# rj45-2x10.net
KiCad netlist of a schematic drawn in EAGLE
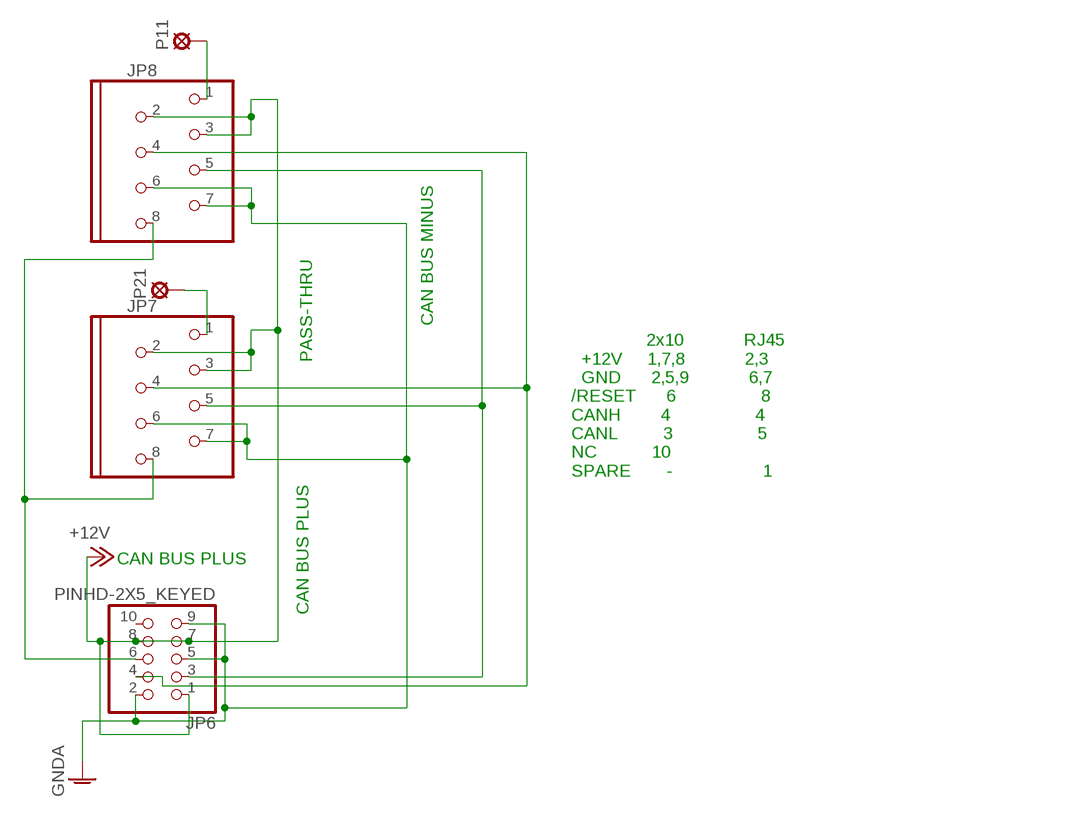
[diagram p0: schematic, sheet 1]

(export (version "E")
  (design (tool "Eeschema 10.0.6"))
  (components
    (comp (ref "JP6")
      (value "PINHD-2X5_KEYED")
      (footprint "eagle-import:2X05_KEYED")
      (libsource (lib "eagle-import") (part "PINHD-2X5_KEYED"))
    )
    (comp (ref "JP7")
      (value "MOD8P8C")
      (footprint "eagle-import:MOD8P8C")
      (libsource (lib "eagle-import") (part "MOD8P8C"))
    )
    (comp (ref "JP8")
      (value "MOD8P8C")
      (footprint "eagle-import:MOD8P8C")
      (libsource (lib "eagle-import") (part "MOD8P8C"))
    )
    (comp (ref "P11")
      (value "SOLPAD035")
      (footprint "eagle-import:SOLDPAD035")
      (libsource (lib "eagle-import") (part "SOLPAD035"))
    )
    (comp (ref "P21")
      (value "SOLPAD035")
      (footprint "eagle-import:SOLDPAD035")
      (libsource (lib "eagle-import") (part "SOLPAD035"))
    )
  )
  (nets
    (net (code "1") (name "+12V") (class "Default")
      (node (ref "JP6") (pin "1") (pinfunction "1_1") (pintype "passive"))
      (node (ref "JP6") (pin "7") (pinfunction "7_7") (pintype "passive"))
      (node (ref "JP6") (pin "8") (pinfunction "8_8") (pintype "passive"))
      (node (ref "JP7") (pin "2") (pinfunction "5_2") (pintype "passive"))
      (node (ref "JP7") (pin "3") (pinfunction "2_3") (pintype "passive"))
      (node (ref "JP8") (pin "2") (pinfunction "5_2") (pintype "passive"))
      (node (ref "JP8") (pin "3") (pinfunction "2_3") (pintype "passive"))
    )
    (net (code "2") (name "GNDA") (class "Default")
      (node (ref "JP6") (pin "2") (pinfunction "2_2") (pintype "passive"))
      (node (ref "JP6") (pin "5") (pinfunction "5_5") (pintype "passive"))
      (node (ref "JP6") (pin "9") (pinfunction "9_9") (pintype "passive"))
      (node (ref "JP7") (pin "6") (pinfunction "7_6") (pintype "passive"))
      (node (ref "JP7") (pin "7") (pinfunction "4_7") (pintype "passive"))
      (node (ref "JP8") (pin "6") (pinfunction "7_6") (pintype "passive"))
      (node (ref "JP8") (pin "7") (pinfunction "4_7") (pintype "passive"))
    )
    (net (code "3") (name "Net-(JP6-Pad6)") (class "Default")
      (node (ref "JP6") (pin "6") (pinfunction "6_6") (pintype "passive"))
      (node (ref "JP7") (pin "8") (pinfunction "8_8") (pintype "passive"))
      (node (ref "JP8") (pin "8") (pinfunction "8_8") (pintype "passive"))
    )
    (net (code "4") (name "Net-(JP7-3)") (class "Default")
      (node (ref "JP6") (pin "3") (pinfunction "3_3") (pintype "passive"))
      (node (ref "JP7") (pin "5") (pinfunction "3_5") (pintype "passive"))
      (node (ref "JP8") (pin "5") (pinfunction "3_5") (pintype "passive"))
    )
    (net (code "5") (name "Net-(JP7-6)") (class "Default")
      (node (ref "JP6") (pin "4") (pinfunction "4_4") (pintype "passive"))
      (node (ref "JP7") (pin "4") (pinfunction "6_4") (pintype "passive"))
      (node (ref "JP8") (pin "4") (pinfunction "6_4") (pintype "passive"))
    )
    (net (code "6") (name "Net-(JP7-Pad1)") (class "Default")
      (node (ref "JP7") (pin "1") (pinfunction "1_1") (pintype "passive"))
      (node (ref "P21") (pin "MP") (pinfunction "MP_MP") (pintype "passive"))
    )
    (net (code "7") (name "Net-(JP8-Pad1)") (class "Default")
      (node (ref "JP8") (pin "1") (pinfunction "1_1") (pintype "passive"))
      (node (ref "P11") (pin "MP") (pinfunction "MP_MP") (pintype "passive"))
    )
    (net (code "8") (name "unconnected-(JP6-Pad10)") (class "Default")
      (node (ref "JP6") (pin "10") (pinfunction "10_10") (pintype "passive"))
    )
  )
)
